# main.net
KiCad netlist of a schematic drawn in EAGLE
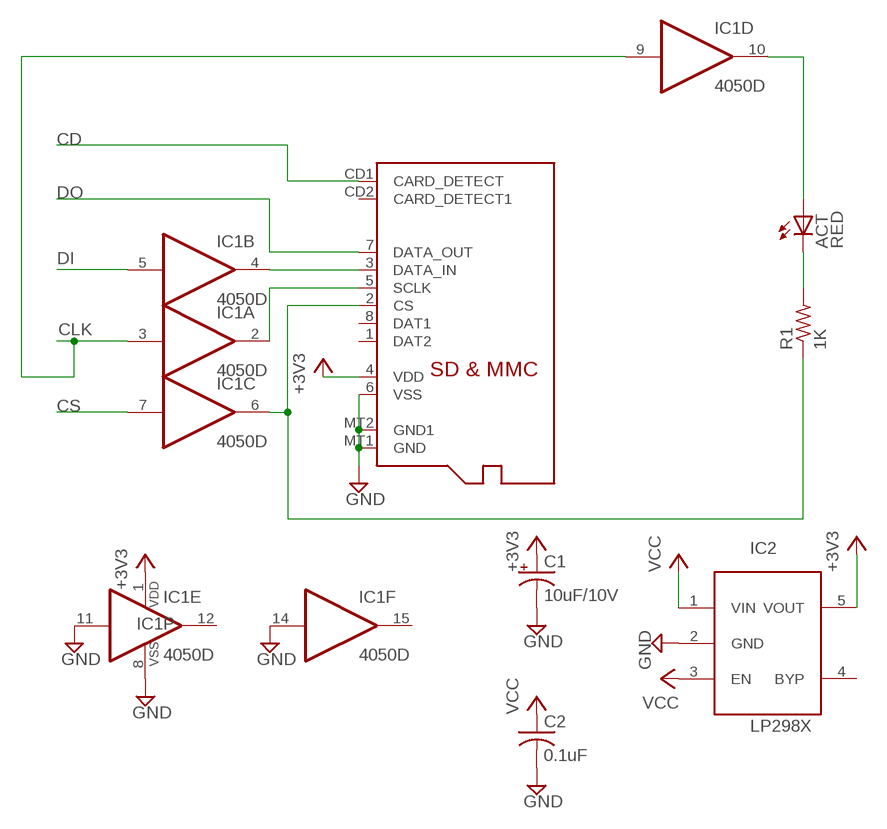
[diagram p0: schematic, sheet 1]

(export (version "E")
  (design (tool "Eeschema 10.0.6"))
  (components
    (comp (ref "ACT")
      (value "RED")
      (footprint "eagle-import:CHIP-LED0805")
      (libsource (lib "eagle-import") (part "LEDCHIP-LED0805"))
    )
    (comp (ref "C1")
      (value "10uF/10V")
      (footprint "eagle-import:A_3216-18R")
      (libsource (lib "eagle-import") (part "CPOL-USA/3216-18R"))
    )
    (comp (ref "C2")
      (value "0.1uF")
      (footprint "eagle-import:C0805K")
      (libsource (lib "eagle-import") (part "C-USC0805K"))
    )
    (comp (ref "IC1")
      (value "4050D")
      (footprint "eagle-import:SO16")
      (libsource (lib "eagle-import") (part "4050D"))
    )
    (comp (ref "IC2")
      (value "LP298XS")
      (footprint "eagle-import:SOT23-5L")
      (libsource (lib "eagle-import") (part "LP298XS"))
    )
    (comp (ref "R1")
      (value "1K")
      (footprint "eagle-import:R0805")
      (libsource (lib "eagle-import") (part "R-US_R0805"))
    )
    (comp (ref "X1")
      (value "MICROSD")
      (footprint "eagle-import:MICROSD")
      (libsource (lib "eagle-import") (part "MICROSD"))
    )
  )
  (nets
    (net (code "1") (name "+3V3") (class "Default")
      (node (ref "C1") (pin "+") (pinfunction "+_+") (pintype "passive"))
      (node (ref "IC1") (pin "1") (pinfunction "VDD_1") (pintype "power_in"))
      (node (ref "IC2") (pin "5") (pinfunction "VOUT_5") (pintype "bidirectional"))
      (node (ref "X1") (pin "4") (pinfunction "VDD_4") (pintype "power_in"))
    )
    (net (code "2") (name "/CD") (class "Default")
      (node (ref "X1") (pin "CD1") (pinfunction "CARD_DETECT_CD1") (pintype "passive"))
    )
    (net (code "3") (name "/CLK") (class "Default")
      (node (ref "IC1") (pin "3") (pinfunction "I_3") (pintype "input"))
      (node (ref "IC1") (pin "9") (pinfunction "I_9") (pintype "input"))
    )
    (net (code "4") (name "/CS") (class "Default")
      (node (ref "IC1") (pin "7") (pinfunction "I_7") (pintype "input"))
    )
    (net (code "5") (name "/DI") (class "Default")
      (node (ref "IC1") (pin "5") (pinfunction "I_5") (pintype "input"))
    )
    (net (code "6") (name "/DO") (class "Default")
      (node (ref "X1") (pin "7") (pinfunction "DATA_OUT_7") (pintype "output"))
    )
    (net (code "7") (name "GND") (class "Default")
      (node (ref "C1") (pin "-") (pinfunction "-_-") (pintype "passive"))
      (node (ref "C2") (pin "2") (pinfunction "2_2") (pintype "passive"))
      (node (ref "IC1") (pin "11") (pinfunction "I_11") (pintype "input"))
      (node (ref "IC1") (pin "14") (pinfunction "I_14") (pintype "input"))
      (node (ref "IC1") (pin "8") (pinfunction "VSS_8") (pintype "power_in"))
      (node (ref "IC2") (pin "2") (pinfunction "GND_2") (pintype "bidirectional"))
      (node (ref "X1") (pin "6") (pinfunction "VSS_6") (pintype "power_in"))
      (node (ref "X1") (pin "MT1") (pinfunction "GND_MT1") (pintype "power_in"))
      (node (ref "X1") (pin "MT2") (pinfunction "GND1_MT2") (pintype "power_in"))
    )
    (net (code "8") (name "Net-(ACT-PadC)") (class "Default")
      (node (ref "ACT") (pin "C") (pinfunction "C_C") (pintype "passive"))
      (node (ref "R1") (pin "2") (pinfunction "2_2") (pintype "passive"))
    )
    (net (code "9") (name "Net-(IC1A-O)") (class "Default")
      (node (ref "IC1") (pin "2") (pinfunction "O_2") (pintype "output"))
      (node (ref "X1") (pin "5") (pinfunction "SCLK_5") (pintype "input"))
    )
    (net (code "10") (name "Net-(IC1B-O)") (class "Default")
      (node (ref "IC1") (pin "4") (pinfunction "O_4") (pintype "output"))
      (node (ref "X1") (pin "3") (pinfunction "DATA_IN_3") (pintype "input"))
    )
    (net (code "11") (name "Net-(IC1C-O)") (class "Default")
      (node (ref "IC1") (pin "6") (pinfunction "O_6") (pintype "output"))
      (node (ref "R1") (pin "1") (pinfunction "1_1") (pintype "passive"))
      (node (ref "X1") (pin "2") (pinfunction "CS_2") (pintype "input"))
    )
    (net (code "12") (name "Net-(IC1D-O)") (class "Default")
      (node (ref "ACT") (pin "A") (pinfunction "A_A") (pintype "passive"))
      (node (ref "IC1") (pin "10") (pinfunction "O_10") (pintype "output"))
    )
    (net (code "13") (name "VCC") (class "Default")
      (node (ref "C2") (pin "1") (pinfunction "1_1") (pintype "passive"))
      (node (ref "IC2") (pin "1") (pinfunction "VIN_1") (pintype "bidirectional"))
      (node (ref "IC2") (pin "3") (pinfunction "EN_3") (pintype "bidirectional"))
    )
    (net (code "14") (name "unconnected-(IC1E-O-Pad12)") (class "Default")
      (node (ref "IC1") (pin "12") (pinfunction "O_12") (pintype "output"))
    )
    (net (code "15") (name "unconnected-(IC1F-O-Pad15)") (class "Default")
      (node (ref "IC1") (pin "15") (pinfunction "O_15") (pintype "output"))
    )
    (net (code "16") (name "unconnected-(IC2-BYP-Pad4)") (class "Default")
      (node (ref "IC2") (pin "4") (pinfunction "BYP_4") (pintype "bidirectional"))
    )
    (net (code "17") (name "unconnected-(X1-CARD_DETECT1-PadCD2)") (class "Default")
      (node (ref "X1") (pin "CD2") (pinfunction "CARD_DETECT1_CD2") (pintype "passive"))
    )
    (net (code "18") (name "unconnected-(X1-DAT1-Pad8)") (class "Default")
      (node (ref "X1") (pin "8") (pinfunction "DAT1_8") (pintype "bidirectional"))
    )
    (net (code "19") (name "unconnected-(X1-DAT2-Pad1)") (class "Default")
      (node (ref "X1") (pin "1") (pinfunction "DAT2_1") (pintype "bidirectional"))
    )
  )
)
